# backplane.net
KiCad netlist of a schematic drawn in EAGLE
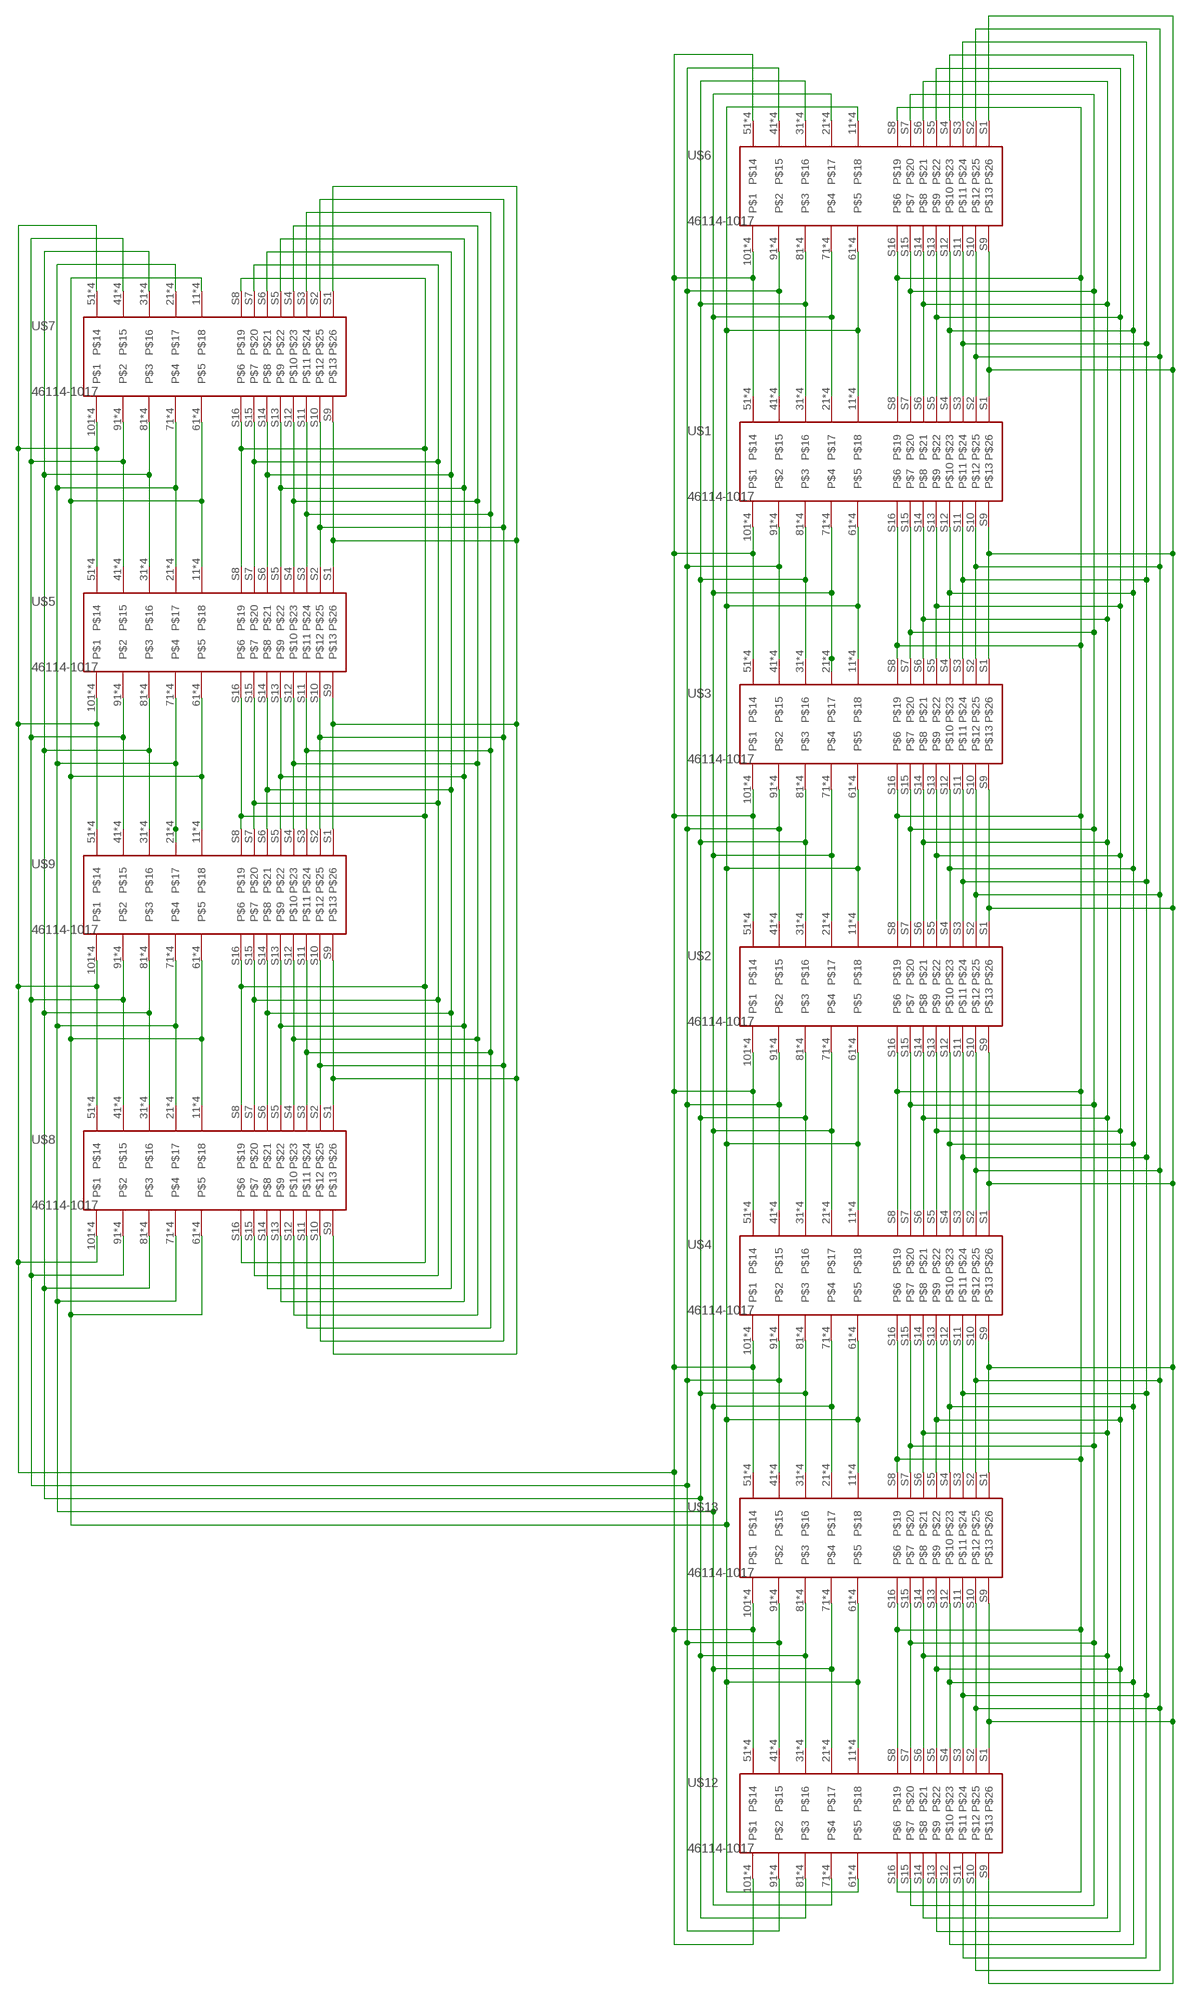
[diagram p0: schematic, sheet 1]

(export (version "E")
  (design (tool "Eeschema 10.0.6"))
  (components
    (comp (ref "U$1")
      (value "46114-1017")
      (footprint "eagle-import:46114-1017")
      (libsource (lib "eagle-import") (part "46114-1017"))
    )
    (comp (ref "U$2")
      (value "46114-1017")
      (footprint "eagle-import:46114-1017")
      (libsource (lib "eagle-import") (part "46114-1017"))
    )
    (comp (ref "U$3")
      (value "46114-1017")
      (footprint "eagle-import:46114-1017")
      (libsource (lib "eagle-import") (part "46114-1017"))
    )
    (comp (ref "U$4")
      (value "46114-1017")
      (footprint "eagle-import:46114-1017")
      (libsource (lib "eagle-import") (part "46114-1017"))
    )
    (comp (ref "U$5")
      (value "46114-1017")
      (footprint "eagle-import:46114-1017")
      (libsource (lib "eagle-import") (part "46114-1017"))
    )
    (comp (ref "U$6")
      (value "46114-1017")
      (footprint "eagle-import:46114-1017")
      (libsource (lib "eagle-import") (part "46114-1017"))
    )
    (comp (ref "U$7")
      (value "46114-1017")
      (footprint "eagle-import:46114-1017")
      (libsource (lib "eagle-import") (part "46114-1017"))
    )
    (comp (ref "U$8")
      (value "46114-1017")
      (footprint "eagle-import:46114-1017")
      (libsource (lib "eagle-import") (part "46114-1017"))
    )
    (comp (ref "U$9")
      (value "46114-1017")
      (footprint "eagle-import:46114-1017")
      (libsource (lib "eagle-import") (part "46114-1017"))
    )
    (comp (ref "U$12")
      (value "46114-1017")
      (footprint "eagle-import:46114-1017")
      (libsource (lib "eagle-import") (part "46114-1017"))
    )
    (comp (ref "U$13")
      (value "46114-1017")
      (footprint "eagle-import:46114-1017")
      (libsource (lib "eagle-import") (part "46114-1017"))
    )
  )
  (nets
    (net (code "1") (name "Net-(U$1-P$1-Pad101)") (class "Default")
      (node (ref "U$1") (pin "101") (pinfunction "P$1_101") (pintype "bidirectional"))
      (node (ref "U$1") (pin "102") (pinfunction "P$1_102") (pintype "bidirectional"))
      (node (ref "U$1") (pin "103") (pinfunction "P$1_103") (pintype "bidirectional"))
      (node (ref "U$1") (pin "104") (pinfunction "P$1_104") (pintype "bidirectional"))
      (node (ref "U$1") (pin "51") (pinfunction "P$14_51") (pintype "bidirectional"))
      (node (ref "U$1") (pin "52") (pinfunction "P$14_52") (pintype "bidirectional"))
      (node (ref "U$1") (pin "53") (pinfunction "P$14_53") (pintype "bidirectional"))
      (node (ref "U$1") (pin "54") (pinfunction "P$14_54") (pintype "bidirectional"))
      (node (ref "U$12") (pin "101") (pinfunction "P$1_101") (pintype "bidirectional"))
      (node (ref "U$12") (pin "102") (pinfunction "P$1_102") (pintype "bidirectional"))
      (node (ref "U$12") (pin "103") (pinfunction "P$1_103") (pintype "bidirectional"))
      (node (ref "U$12") (pin "104") (pinfunction "P$1_104") (pintype "bidirectional"))
      (node (ref "U$12") (pin "51") (pinfunction "P$14_51") (pintype "bidirectional"))
      (node (ref "U$12") (pin "52") (pinfunction "P$14_52") (pintype "bidirectional"))
      (node (ref "U$12") (pin "53") (pinfunction "P$14_53") (pintype "bidirectional"))
      (node (ref "U$12") (pin "54") (pinfunction "P$14_54") (pintype "bidirectional"))
      (node (ref "U$13") (pin "101") (pinfunction "P$1_101") (pintype "bidirectional"))
      (node (ref "U$13") (pin "102") (pinfunction "P$1_102") (pintype "bidirectional"))
      (node (ref "U$13") (pin "103") (pinfunction "P$1_103") (pintype "bidirectional"))
      (node (ref "U$13") (pin "104") (pinfunction "P$1_104") (pintype "bidirectional"))
      (node (ref "U$13") (pin "51") (pinfunction "P$14_51") (pintype "bidirectional"))
      (node (ref "U$13") (pin "52") (pinfunction "P$14_52") (pintype "bidirectional"))
      (node (ref "U$13") (pin "53") (pinfunction "P$14_53") (pintype "bidirectional"))
      (node (ref "U$13") (pin "54") (pinfunction "P$14_54") (pintype "bidirectional"))
      (node (ref "U$2") (pin "101") (pinfunction "P$1_101") (pintype "bidirectional"))
      (node (ref "U$2") (pin "102") (pinfunction "P$1_102") (pintype "bidirectional"))
      (node (ref "U$2") (pin "103") (pinfunction "P$1_103") (pintype "bidirectional"))
      (node (ref "U$2") (pin "104") (pinfunction "P$1_104") (pintype "bidirectional"))
      (node (ref "U$2") (pin "51") (pinfunction "P$14_51") (pintype "bidirectional"))
      (node (ref "U$2") (pin "52") (pinfunction "P$14_52") (pintype "bidirectional"))
      (node (ref "U$2") (pin "53") (pinfunction "P$14_53") (pintype "bidirectional"))
      (node (ref "U$2") (pin "54") (pinfunction "P$14_54") (pintype "bidirectional"))
      (node (ref "U$3") (pin "101") (pinfunction "P$1_101") (pintype "bidirectional"))
      (node (ref "U$3") (pin "102") (pinfunction "P$1_102") (pintype "bidirectional"))
      (node (ref "U$3") (pin "103") (pinfunction "P$1_103") (pintype "bidirectional"))
      (node (ref "U$3") (pin "104") (pinfunction "P$1_104") (pintype "bidirectional"))
      (node (ref "U$3") (pin "51") (pinfunction "P$14_51") (pintype "bidirectional"))
      (node (ref "U$3") (pin "52") (pinfunction "P$14_52") (pintype "bidirectional"))
      (node (ref "U$3") (pin "53") (pinfunction "P$14_53") (pintype "bidirectional"))
      (node (ref "U$3") (pin "54") (pinfunction "P$14_54") (pintype "bidirectional"))
      (node (ref "U$4") (pin "101") (pinfunction "P$1_101") (pintype "bidirectional"))
      (node (ref "U$4") (pin "102") (pinfunction "P$1_102") (pintype "bidirectional"))
      (node (ref "U$4") (pin "103") (pinfunction "P$1_103") (pintype "bidirectional"))
      (node (ref "U$4") (pin "104") (pinfunction "P$1_104") (pintype "bidirectional"))
      (node (ref "U$4") (pin "51") (pinfunction "P$14_51") (pintype "bidirectional"))
      (node (ref "U$4") (pin "52") (pinfunction "P$14_52") (pintype "bidirectional"))
      (node (ref "U$4") (pin "53") (pinfunction "P$14_53") (pintype "bidirectional"))
      (node (ref "U$4") (pin "54") (pinfunction "P$14_54") (pintype "bidirectional"))
      (node (ref "U$5") (pin "101") (pinfunction "P$1_101") (pintype "bidirectional"))
      (node (ref "U$5") (pin "102") (pinfunction "P$1_102") (pintype "bidirectional"))
      (node (ref "U$5") (pin "103") (pinfunction "P$1_103") (pintype "bidirectional"))
      (node (ref "U$5") (pin "104") (pinfunction "P$1_104") (pintype "bidirectional"))
      (node (ref "U$5") (pin "51") (pinfunction "P$14_51") (pintype "bidirectional"))
      (node (ref "U$5") (pin "52") (pinfunction "P$14_52") (pintype "bidirectional"))
      (node (ref "U$5") (pin "53") (pinfunction "P$14_53") (pintype "bidirectional"))
      (node (ref "U$5") (pin "54") (pinfunction "P$14_54") (pintype "bidirectional"))
      (node (ref "U$6") (pin "101") (pinfunction "P$1_101") (pintype "bidirectional"))
      (node (ref "U$6") (pin "102") (pinfunction "P$1_102") (pintype "bidirectional"))
      (node (ref "U$6") (pin "103") (pinfunction "P$1_103") (pintype "bidirectional"))
      (node (ref "U$6") (pin "104") (pinfunction "P$1_104") (pintype "bidirectional"))
      (node (ref "U$6") (pin "51") (pinfunction "P$14_51") (pintype "bidirectional"))
      (node (ref "U$6") (pin "52") (pinfunction "P$14_52") (pintype "bidirectional"))
      (node (ref "U$6") (pin "53") (pinfunction "P$14_53") (pintype "bidirectional"))
      (node (ref "U$6") (pin "54") (pinfunction "P$14_54") (pintype "bidirectional"))
      (node (ref "U$7") (pin "101") (pinfunction "P$1_101") (pintype "bidirectional"))
      (node (ref "U$7") (pin "102") (pinfunction "P$1_102") (pintype "bidirectional"))
      (node (ref "U$7") (pin "103") (pinfunction "P$1_103") (pintype "bidirectional"))
      (node (ref "U$7") (pin "104") (pinfunction "P$1_104") (pintype "bidirectional"))
      (node (ref "U$7") (pin "51") (pinfunction "P$14_51") (pintype "bidirectional"))
      (node (ref "U$7") (pin "52") (pinfunction "P$14_52") (pintype "bidirectional"))
      (node (ref "U$7") (pin "53") (pinfunction "P$14_53") (pintype "bidirectional"))
      (node (ref "U$7") (pin "54") (pinfunction "P$14_54") (pintype "bidirectional"))
      (node (ref "U$8") (pin "101") (pinfunction "P$1_101") (pintype "bidirectional"))
      (node (ref "U$8") (pin "102") (pinfunction "P$1_102") (pintype "bidirectional"))
      (node (ref "U$8") (pin "103") (pinfunction "P$1_103") (pintype "bidirectional"))
      (node (ref "U$8") (pin "104") (pinfunction "P$1_104") (pintype "bidirectional"))
      (node (ref "U$8") (pin "51") (pinfunction "P$14_51") (pintype "bidirectional"))
      (node (ref "U$8") (pin "52") (pinfunction "P$14_52") (pintype "bidirectional"))
      (node (ref "U$8") (pin "53") (pinfunction "P$14_53") (pintype "bidirectional"))
      (node (ref "U$8") (pin "54") (pinfunction "P$14_54") (pintype "bidirectional"))
      (node (ref "U$9") (pin "101") (pinfunction "P$1_101") (pintype "bidirectional"))
      (node (ref "U$9") (pin "102") (pinfunction "P$1_102") (pintype "bidirectional"))
      (node (ref "U$9") (pin "103") (pinfunction "P$1_103") (pintype "bidirectional"))
      (node (ref "U$9") (pin "104") (pinfunction "P$1_104") (pintype "bidirectional"))
      (node (ref "U$9") (pin "51") (pinfunction "P$14_51") (pintype "bidirectional"))
      (node (ref "U$9") (pin "52") (pinfunction "P$14_52") (pintype "bidirectional"))
      (node (ref "U$9") (pin "53") (pinfunction "P$14_53") (pintype "bidirectional"))
      (node (ref "U$9") (pin "54") (pinfunction "P$14_54") (pintype "bidirectional"))
    )
    (net (code "2") (name "Net-(U$1-P$10)") (class "Default")
      (node (ref "U$1") (pin "S12") (pinfunction "P$10_S12") (pintype "bidirectional"))
      (node (ref "U$1") (pin "S4") (pinfunction "P$23_S4") (pintype "bidirectional"))
      (node (ref "U$12") (pin "S12") (pinfunction "P$10_S12") (pintype "bidirectional"))
      (node (ref "U$12") (pin "S4") (pinfunction "P$23_S4") (pintype "bidirectional"))
      (node (ref "U$13") (pin "S12") (pinfunction "P$10_S12") (pintype "bidirectional"))
      (node (ref "U$13") (pin "S4") (pinfunction "P$23_S4") (pintype "bidirectional"))
      (node (ref "U$2") (pin "S12") (pinfunction "P$10_S12") (pintype "bidirectional"))
      (node (ref "U$2") (pin "S4") (pinfunction "P$23_S4") (pintype "bidirectional"))
      (node (ref "U$3") (pin "S12") (pinfunction "P$10_S12") (pintype "bidirectional"))
      (node (ref "U$3") (pin "S4") (pinfunction "P$23_S4") (pintype "bidirectional"))
      (node (ref "U$4") (pin "S12") (pinfunction "P$10_S12") (pintype "bidirectional"))
      (node (ref "U$4") (pin "S4") (pinfunction "P$23_S4") (pintype "bidirectional"))
      (node (ref "U$6") (pin "S12") (pinfunction "P$10_S12") (pintype "bidirectional"))
      (node (ref "U$6") (pin "S4") (pinfunction "P$23_S4") (pintype "bidirectional"))
    )
    (net (code "3") (name "Net-(U$1-P$11)") (class "Default")
      (node (ref "U$1") (pin "S11") (pinfunction "P$11_S11") (pintype "bidirectional"))
      (node (ref "U$1") (pin "S3") (pinfunction "P$24_S3") (pintype "bidirectional"))
      (node (ref "U$12") (pin "S11") (pinfunction "P$11_S11") (pintype "bidirectional"))
      (node (ref "U$12") (pin "S3") (pinfunction "P$24_S3") (pintype "bidirectional"))
      (node (ref "U$13") (pin "S11") (pinfunction "P$11_S11") (pintype "bidirectional"))
      (node (ref "U$13") (pin "S3") (pinfunction "P$24_S3") (pintype "bidirectional"))
      (node (ref "U$2") (pin "S11") (pinfunction "P$11_S11") (pintype "bidirectional"))
      (node (ref "U$2") (pin "S3") (pinfunction "P$24_S3") (pintype "bidirectional"))
      (node (ref "U$3") (pin "S11") (pinfunction "P$11_S11") (pintype "bidirectional"))
      (node (ref "U$3") (pin "S3") (pinfunction "P$24_S3") (pintype "bidirectional"))
      (node (ref "U$4") (pin "S11") (pinfunction "P$11_S11") (pintype "bidirectional"))
      (node (ref "U$4") (pin "S3") (pinfunction "P$24_S3") (pintype "bidirectional"))
      (node (ref "U$6") (pin "S11") (pinfunction "P$11_S11") (pintype "bidirectional"))
      (node (ref "U$6") (pin "S3") (pinfunction "P$24_S3") (pintype "bidirectional"))
    )
    (net (code "4") (name "Net-(U$1-P$12)") (class "Default")
      (node (ref "U$1") (pin "S10") (pinfunction "P$12_S10") (pintype "bidirectional"))
      (node (ref "U$1") (pin "S2") (pinfunction "P$25_S2") (pintype "bidirectional"))
      (node (ref "U$12") (pin "S10") (pinfunction "P$12_S10") (pintype "bidirectional"))
      (node (ref "U$12") (pin "S2") (pinfunction "P$25_S2") (pintype "bidirectional"))
      (node (ref "U$13") (pin "S10") (pinfunction "P$12_S10") (pintype "bidirectional"))
      (node (ref "U$13") (pin "S2") (pinfunction "P$25_S2") (pintype "bidirectional"))
      (node (ref "U$2") (pin "S10") (pinfunction "P$12_S10") (pintype "bidirectional"))
      (node (ref "U$2") (pin "S2") (pinfunction "P$25_S2") (pintype "bidirectional"))
      (node (ref "U$3") (pin "S10") (pinfunction "P$12_S10") (pintype "bidirectional"))
      (node (ref "U$3") (pin "S2") (pinfunction "P$25_S2") (pintype "bidirectional"))
      (node (ref "U$4") (pin "S10") (pinfunction "P$12_S10") (pintype "bidirectional"))
      (node (ref "U$4") (pin "S2") (pinfunction "P$25_S2") (pintype "bidirectional"))
      (node (ref "U$6") (pin "S10") (pinfunction "P$12_S10") (pintype "bidirectional"))
      (node (ref "U$6") (pin "S2") (pinfunction "P$25_S2") (pintype "bidirectional"))
    )
    (net (code "5") (name "Net-(U$1-P$13)") (class "Default")
      (node (ref "U$1") (pin "S1") (pinfunction "P$26_S1") (pintype "bidirectional"))
      (node (ref "U$1") (pin "S9") (pinfunction "P$13_S9") (pintype "bidirectional"))
      (node (ref "U$12") (pin "S1") (pinfunction "P$26_S1") (pintype "bidirectional"))
      (node (ref "U$12") (pin "S9") (pinfunction "P$13_S9") (pintype "bidirectional"))
      (node (ref "U$13") (pin "S1") (pinfunction "P$26_S1") (pintype "bidirectional"))
      (node (ref "U$13") (pin "S9") (pinfunction "P$13_S9") (pintype "bidirectional"))
      (node (ref "U$2") (pin "S1") (pinfunction "P$26_S1") (pintype "bidirectional"))
      (node (ref "U$2") (pin "S9") (pinfunction "P$13_S9") (pintype "bidirectional"))
      (node (ref "U$3") (pin "S1") (pinfunction "P$26_S1") (pintype "bidirectional"))
      (node (ref "U$3") (pin "S9") (pinfunction "P$13_S9") (pintype "bidirectional"))
      (node (ref "U$4") (pin "S1") (pinfunction "P$26_S1") (pintype "bidirectional"))
      (node (ref "U$4") (pin "S9") (pinfunction "P$13_S9") (pintype "bidirectional"))
      (node (ref "U$6") (pin "S1") (pinfunction "P$26_S1") (pintype "bidirectional"))
      (node (ref "U$6") (pin "S9") (pinfunction "P$13_S9") (pintype "bidirectional"))
    )
    (net (code "6") (name "Net-(U$1-P$15-Pad41)") (class "Default")
      (node (ref "U$1") (pin "41") (pinfunction "P$15_41") (pintype "bidirectional"))
      (node (ref "U$1") (pin "42") (pinfunction "P$15_42") (pintype "bidirectional"))
      (node (ref "U$1") (pin "43") (pinfunction "P$15_43") (pintype "bidirectional"))
      (node (ref "U$1") (pin "44") (pinfunction "P$15_44") (pintype "bidirectional"))
      (node (ref "U$1") (pin "91") (pinfunction "P$2_91") (pintype "bidirectional"))
      (node (ref "U$1") (pin "92") (pinfunction "P$2_92") (pintype "bidirectional"))
      (node (ref "U$1") (pin "93") (pinfunction "P$2_93") (pintype "bidirectional"))
      (node (ref "U$1") (pin "94") (pinfunction "P$2_94") (pintype "bidirectional"))
      (node (ref "U$12") (pin "41") (pinfunction "P$15_41") (pintype "bidirectional"))
      (node (ref "U$12") (pin "42") (pinfunction "P$15_42") (pintype "bidirectional"))
      (node (ref "U$12") (pin "43") (pinfunction "P$15_43") (pintype "bidirectional"))
      (node (ref "U$12") (pin "44") (pinfunction "P$15_44") (pintype "bidirectional"))
      (node (ref "U$12") (pin "91") (pinfunction "P$2_91") (pintype "bidirectional"))
      (node (ref "U$12") (pin "92") (pinfunction "P$2_92") (pintype "bidirectional"))
      (node (ref "U$12") (pin "93") (pinfunction "P$2_93") (pintype "bidirectional"))
      (node (ref "U$12") (pin "94") (pinfunction "P$2_94") (pintype "bidirectional"))
      (node (ref "U$13") (pin "41") (pinfunction "P$15_41") (pintype "bidirectional"))
      (node (ref "U$13") (pin "42") (pinfunction "P$15_42") (pintype "bidirectional"))
      (node (ref "U$13") (pin "43") (pinfunction "P$15_43") (pintype "bidirectional"))
      (node (ref "U$13") (pin "44") (pinfunction "P$15_44") (pintype "bidirectional"))
      (node (ref "U$13") (pin "91") (pinfunction "P$2_91") (pintype "bidirectional"))
      (node (ref "U$13") (pin "92") (pinfunction "P$2_92") (pintype "bidirectional"))
      (node (ref "U$13") (pin "93") (pinfunction "P$2_93") (pintype "bidirectional"))
      (node (ref "U$13") (pin "94") (pinfunction "P$2_94") (pintype "bidirectional"))
      (node (ref "U$2") (pin "41") (pinfunction "P$15_41") (pintype "bidirectional"))
      (node (ref "U$2") (pin "42") (pinfunction "P$15_42") (pintype "bidirectional"))
      (node (ref "U$2") (pin "43") (pinfunction "P$15_43") (pintype "bidirectional"))
      (node (ref "U$2") (pin "44") (pinfunction "P$15_44") (pintype "bidirectional"))
      (node (ref "U$2") (pin "91") (pinfunction "P$2_91") (pintype "bidirectional"))
      (node (ref "U$2") (pin "92") (pinfunction "P$2_92") (pintype "bidirectional"))
      (node (ref "U$2") (pin "93") (pinfunction "P$2_93") (pintype "bidirectional"))
      (node (ref "U$2") (pin "94") (pinfunction "P$2_94") (pintype "bidirectional"))
      (node (ref "U$3") (pin "41") (pinfunction "P$15_41") (pintype "bidirectional"))
      (node (ref "U$3") (pin "42") (pinfunction "P$15_42") (pintype "bidirectional"))
      (node (ref "U$3") (pin "43") (pinfunction "P$15_43") (pintype "bidirectional"))
      (node (ref "U$3") (pin "44") (pinfunction "P$15_44") (pintype "bidirectional"))
      (node (ref "U$3") (pin "91") (pinfunction "P$2_91") (pintype "bidirectional"))
      (node (ref "U$3") (pin "92") (pinfunction "P$2_92") (pintype "bidirectional"))
      (node (ref "U$3") (pin "93") (pinfunction "P$2_93") (pintype "bidirectional"))
      (node (ref "U$3") (pin "94") (pinfunction "P$2_94") (pintype "bidirectional"))
      (node (ref "U$4") (pin "41") (pinfunction "P$15_41") (pintype "bidirectional"))
      (node (ref "U$4") (pin "42") (pinfunction "P$15_42") (pintype "bidirectional"))
      (node (ref "U$4") (pin "43") (pinfunction "P$15_43") (pintype "bidirectional"))
      (node (ref "U$4") (pin "44") (pinfunction "P$15_44") (pintype "bidirectional"))
      (node (ref "U$4") (pin "91") (pinfunction "P$2_91") (pintype "bidirectional"))
      (node (ref "U$4") (pin "92") (pinfunction "P$2_92") (pintype "bidirectional"))
      (node (ref "U$4") (pin "93") (pinfunction "P$2_93") (pintype "bidirectional"))
      (node (ref "U$4") (pin "94") (pinfunction "P$2_94") (pintype "bidirectional"))
      (node (ref "U$5") (pin "41") (pinfunction "P$15_41") (pintype "bidirectional"))
      (node (ref "U$5") (pin "42") (pinfunction "P$15_42") (pintype "bidirectional"))
      (node (ref "U$5") (pin "43") (pinfunction "P$15_43") (pintype "bidirectional"))
      (node (ref "U$5") (pin "44") (pinfunction "P$15_44") (pintype "bidirectional"))
      (node (ref "U$5") (pin "91") (pinfunction "P$2_91") (pintype "bidirectional"))
      (node (ref "U$5") (pin "92") (pinfunction "P$2_92") (pintype "bidirectional"))
      (node (ref "U$5") (pin "93") (pinfunction "P$2_93") (pintype "bidirectional"))
      (node (ref "U$5") (pin "94") (pinfunction "P$2_94") (pintype "bidirectional"))
      (node (ref "U$6") (pin "41") (pinfunction "P$15_41") (pintype "bidirectional"))
      (node (ref "U$6") (pin "42") (pinfunction "P$15_42") (pintype "bidirectional"))
      (node (ref "U$6") (pin "43") (pinfunction "P$15_43") (pintype "bidirectional"))
      (node (ref "U$6") (pin "44") (pinfunction "P$15_44") (pintype "bidirectional"))
      (node (ref "U$6") (pin "91") (pinfunction "P$2_91") (pintype "bidirectional"))
      (node (ref "U$6") (pin "92") (pinfunction "P$2_92") (pintype "bidirectional"))
      (node (ref "U$6") (pin "93") (pinfunction "P$2_93") (pintype "bidirectional"))
      (node (ref "U$6") (pin "94") (pinfunction "P$2_94") (pintype "bidirectional"))
      (node (ref "U$7") (pin "41") (pinfunction "P$15_41") (pintype "bidirectional"))
      (node (ref "U$7") (pin "42") (pinfunction "P$15_42") (pintype "bidirectional"))
      (node (ref "U$7") (pin "43") (pinfunction "P$15_43") (pintype "bidirectional"))
      (node (ref "U$7") (pin "44") (pinfunction "P$15_44") (pintype "bidirectional"))
      (node (ref "U$7") (pin "91") (pinfunction "P$2_91") (pintype "bidirectional"))
      (node (ref "U$7") (pin "92") (pinfunction "P$2_92") (pintype "bidirectional"))
      (node (ref "U$7") (pin "93") (pinfunction "P$2_93") (pintype "bidirectional"))
      (node (ref "U$7") (pin "94") (pinfunction "P$2_94") (pintype "bidirectional"))
      (node (ref "U$8") (pin "41") (pinfunction "P$15_41") (pintype "bidirectional"))
      (node (ref "U$8") (pin "42") (pinfunction "P$15_42") (pintype "bidirectional"))
      (node (ref "U$8") (pin "43") (pinfunction "P$15_43") (pintype "bidirectional"))
      (node (ref "U$8") (pin "44") (pinfunction "P$15_44") (pintype "bidirectional"))
      (node (ref "U$8") (pin "91") (pinfunction "P$2_91") (pintype "bidirectional"))
      (node (ref "U$8") (pin "92") (pinfunction "P$2_92") (pintype "bidirectional"))
      (node (ref "U$8") (pin "93") (pinfunction "P$2_93") (pintype "bidirectional"))
      (node (ref "U$8") (pin "94") (pinfunction "P$2_94") (pintype "bidirectional"))
      (node (ref "U$9") (pin "41") (pinfunction "P$15_41") (pintype "bidirectional"))
      (node (ref "U$9") (pin "42") (pinfunction "P$15_42") (pintype "bidirectional"))
      (node (ref "U$9") (pin "43") (pinfunction "P$15_43") (pintype "bidirectional"))
      (node (ref "U$9") (pin "44") (pinfunction "P$15_44") (pintype "bidirectional"))
      (node (ref "U$9") (pin "91") (pinfunction "P$2_91") (pintype "bidirectional"))
      (node (ref "U$9") (pin "92") (pinfunction "P$2_92") (pintype "bidirectional"))
      (node (ref "U$9") (pin "93") (pinfunction "P$2_93") (pintype "bidirectional"))
      (node (ref "U$9") (pin "94") (pinfunction "P$2_94") (pintype "bidirectional"))
    )
    (net (code "7") (name "Net-(U$1-P$16-Pad31)") (class "Default")
      (node (ref "U$1") (pin "31") (pinfunction "P$16_31") (pintype "bidirectional"))
      (node (ref "U$1") (pin "32") (pinfunction "P$16_32") (pintype "bidirectional"))
      (node (ref "U$1") (pin "33") (pinfunction "P$16_33") (pintype "bidirectional"))
      (node (ref "U$1") (pin "34") (pinfunction "P$16_34") (pintype "bidirectional"))
      (node (ref "U$1") (pin "81") (pinfunction "P$3_81") (pintype "bidirectional"))
      (node (ref "U$1") (pin "82") (pinfunction "P$3_82") (pintype "bidirectional"))
      (node (ref "U$1") (pin "83") (pinfunction "P$3_83") (pintype "bidirectional"))
      (node (ref "U$1") (pin "84") (pinfunction "P$3_84") (pintype "bidirectional"))
      (node (ref "U$12") (pin "31") (pinfunction "P$16_31") (pintype "bidirectional"))
      (node (ref "U$12") (pin "32") (pinfunction "P$16_32") (pintype "bidirectional"))
      (node (ref "U$12") (pin "33") (pinfunction "P$16_33") (pintype "bidirectional"))
      (node (ref "U$12") (pin "34") (pinfunction "P$16_34") (pintype "bidirectional"))
      (node (ref "U$12") (pin "81") (pinfunction "P$3_81") (pintype "bidirectional"))
      (node (ref "U$12") (pin "82") (pinfunction "P$3_82") (pintype "bidirectional"))
      (node (ref "U$12") (pin "83") (pinfunction "P$3_83") (pintype "bidirectional"))
      (node (ref "U$12") (pin "84") (pinfunction "P$3_84") (pintype "bidirectional"))
      (node (ref "U$13") (pin "31") (pinfunction "P$16_31") (pintype "bidirectional"))
      (node (ref "U$13") (pin "32") (pinfunction "P$16_32") (pintype "bidirectional"))
      (node (ref "U$13") (pin "33") (pinfunction "P$16_33") (pintype "bidirectional"))
      (node (ref "U$13") (pin "34") (pinfunction "P$16_34") (pintype "bidirectional"))
      (node (ref "U$13") (pin "81") (pinfunction "P$3_81") (pintype "bidirectional"))
      (node (ref "U$13") (pin "82") (pinfunction "P$3_82") (pintype "bidirectional"))
      (node (ref "U$13") (pin "83") (pinfunction "P$3_83") (pintype "bidirectional"))
      (node (ref "U$13") (pin "84") (pinfunction "P$3_84") (pintype "bidirectional"))
      (node (ref "U$2") (pin "31") (pinfunction "P$16_31") (pintype "bidirectional"))
      (node (ref "U$2") (pin "32") (pinfunction "P$16_32") (pintype "bidirectional"))
      (node (ref "U$2") (pin "33") (pinfunction "P$16_33") (pintype "bidirectional"))
      (node (ref "U$2") (pin "34") (pinfunction "P$16_34") (pintype "bidirectional"))
      (node (ref "U$2") (pin "81") (pinfunction "P$3_81") (pintype "bidirectional"))
      (node (ref "U$2") (pin "82") (pinfunction "P$3_82") (pintype "bidirectional"))
      (node (ref "U$2") (pin "83") (pinfunction "P$3_83") (pintype "bidirectional"))
      (node (ref "U$2") (pin "84") (pinfunction "P$3_84") (pintype "bidirectional"))
      (node (ref "U$3") (pin "31") (pinfunction "P$16_31") (pintype "bidirectional"))
      (node (ref "U$3") (pin "32") (pinfunction "P$16_32") (pintype "bidirectional"))
      (node (ref "U$3") (pin "33") (pinfunction "P$16_33") (pintype "bidirectional"))
      (node (ref "U$3") (pin "34") (pinfunction "P$16_34") (pintype "bidirectional"))
      (node (ref "U$3") (pin "81") (pinfunction "P$3_81") (pintype "bidirectional"))
      (node (ref "U$3") (pin "82") (pinfunction "P$3_82") (pintype "bidirectional"))
      (node (ref "U$3") (pin "83") (pinfunction "P$3_83") (pintype "bidirectional"))
      (node (ref "U$3") (pin "84") (pinfunction "P$3_84") (pintype "bidirectional"))
      (node (ref "U$4") (pin "31") (pinfunction "P$16_31") (pintype "bidirectional"))
      (node (ref "U$4") (pin "32") (pinfunction "P$16_32") (pintype "bidirectional"))
      (node (ref "U$4") (pin "33") (pinfunction "P$16_33") (pintype "bidirectional"))
      (node (ref "U$4") (pin "34") (pinfunction "P$16_34") (pintype "bidirectional"))
      (node (ref "U$4") (pin "81") (pinfunction "P$3_81") (pintype "bidirectional"))
      (node (ref "U$4") (pin "82") (pinfunction "P$3_82") (pintype "bidirectional"))
      (node (ref "U$4") (pin "83") (pinfunction "P$3_83") (pintype "bidirectional"))
      (node (ref "U$4") (pin "84") (pinfunction "P$3_84") (pintype "bidirectional"))
      (node (ref "U$5") (pin "31") (pinfunction "P$16_31") (pintype "bidirectional"))
      (node (ref "U$5") (pin "32") (pinfunction "P$16_32") (pintype "bidirectional"))
      (node (ref "U$5") (pin "33") (pinfunction "P$16_33") (pintype "bidirectional"))
      (node (ref "U$5") (pin "34") (pinfunction "P$16_34") (pintype "bidirectional"))
      (node (ref "U$5") (pin "81") (pinfunction "P$3_81") (pintype "bidirectional"))
      (node (ref "U$5") (pin "82") (pinfunction "P$3_82") (pintype "bidirectional"))
      (node (ref "U$5") (pin "83") (pinfunction "P$3_83") (pintype "bidirectional"))
      (node (ref "U$5") (pin "84") (pinfunction "P$3_84") (pintype "bidirectional"))
      (node (ref "U$6") (pin "31") (pinfunction "P$16_31") (pintype "bidirectional"))
      (node (ref "U$6") (pin "32") (pinfunction "P$16_32") (pintype "bidirectional"))
      (node (ref "U$6") (pin "33") (pinfunction "P$16_33") (pintype "bidirectional"))
      (node (ref "U$6") (pin "34") (pinfunction "P$16_34") (pintype "bidirectional"))
      (node (ref "U$6") (pin "81") (pinfunction "P$3_81") (pintype "bidirectional"))
      (node (ref "U$6") (pin "82") (pinfunction "P$3_82") (pintype "bidirectional"))
      (node (ref "U$6") (pin "83") (pinfunction "P$3_83") (pintype "bidirectional"))
      (node (ref "U$6") (pin "84") (pinfunction "P$3_84") (pintype "bidirectional"))
      (node (ref "U$7") (pin "31") (pinfunction "P$16_31") (pintype "bidirectional"))
      (node (ref "U$7") (pin "32") (pinfunction "P$16_32") (pintype "bidirectional"))
      (node (ref "U$7") (pin "33") (pinfunction "P$16_33") (pintype "bidirectional"))
      (node (ref "U$7") (pin "34") (pinfunction "P$16_34") (pintype "bidirectional"))
      (node (ref "U$7") (pin "81") (pinfunction "P$3_81") (pintype "bidirectional"))
      (node (ref "U$7") (pin "82") (pinfunction "P$3_82") (pintype "bidirectional"))
      (node (ref "U$7") (pin "83") (pinfunction "P$3_83") (pintype "bidirectional"))
      (node (ref "U$7") (pin "84") (pinfunction "P$3_84") (pintype "bidirectional"))
      (node (ref "U$8") (pin "31") (pinfunction "P$16_31") (pintype "bidirectional"))
      (node (ref "U$8") (pin "32") (pinfunction "P$16_32") (pintype "bidirectional"))
      (node (ref "U$8") (pin "33") (pinfunction "P$16_33") (pintype "bidirectional"))
      (node (ref "U$8") (pin "34") (pinfunction "P$16_34") (pintype "bidirectional"))
      (node (ref "U$8") (pin "81") (pinfunction "P$3_81") (pintype "bidirectional"))
      (node (ref "U$8") (pin "82") (pinfunction "P$3_82") (pintype "bidirectional"))
      (node (ref "U$8") (pin "83") (pinfunction "P$3_83") (pintype "bidirectional"))
      (node (ref "U$8") (pin "84") (pinfunction "P$3_84") (pintype "bidirectional"))
      (node (ref "U$9") (pin "31") (pinfunction "P$16_31") (pintype "bidirectional"))
      (node (ref "U$9") (pin "32") (pinfunction "P$16_32") (pintype "bidirectional"))
      (node (ref "U$9") (pin "33") (pinfunction "P$16_33") (pintype "bidirectional"))
      (node (ref "U$9") (pin "34") (pinfunction "P$16_34") (pintype "bidirectional"))
      (node (ref "U$9") (pin "81") (pinfunction "P$3_81") (pintype "bidirectional"))
      (node (ref "U$9") (pin "82") (pinfunction "P$3_82") (pintype "bidirectional"))
      (node (ref "U$9") (pin "83") (pinfunction "P$3_83") (pintype "bidirectional"))
      (node (ref "U$9") (pin "84") (pinfunction "P$3_84") (pintype "bidirectional"))
    )
    (net (code "8") (name "Net-(U$1-P$17-Pad21)") (class "Default")
      (node (ref "U$1") (pin "21") (pinfunction "P$17_21") (pintype "bidirectional"))
      (node (ref "U$1") (pin "22") (pinfunction "P$17_22") (pintype "bidirectional"))
      (node (ref "U$1") (pin "23") (pinfunction "P$17_23") (pintype "bidirectional"))
      (node (ref "U$1") (pin "24") (pinfunction "P$17_24") (pintype "bidirectional"))
      (node (ref "U$1") (pin "71") (pinfunction "P$4_71") (pintype "bidirectional"))
      (node (ref "U$1") (pin "72") (pinfunction "P$4_72") (pintype "bidirectional"))
      (node (ref "U$1") (pin "73") (pinfunction "P$4_73") (pintype "bidirectional"))
      (node (ref "U$1") (pin "74") (pinfunction "P$4_74") (pintype "bidirectional"))
      (node (ref "U$12") (pin "21") (pinfunction "P$17_21") (pintype "bidirectional"))
      (node (ref "U$12") (pin "22") (pinfunction "P$17_22") (pintype "bidirectional"))
      (node (ref "U$12") (pin "23") (pinfunction "P$17_23") (pintype "bidirectional"))
      (node (ref "U$12") (pin "24") (pinfunction "P$17_24") (pintype "bidirectional"))
      (node (ref "U$12") (pin "71") (pinfunction "P$4_71") (pintype "bidirectional"))
      (node (ref "U$12") (pin "72") (pinfunction "P$4_72") (pintype "bidirectional"))
      (node (ref "U$12") (pin "73") (pinfunction "P$4_73") (pintype "bidirectional"))
      (node (ref "U$12") (pin "74") (pinfunction "P$4_74") (pintype "bidirectional"))
      (node (ref "U$13") (pin "21") (pinfunction "P$17_21") (pintype "bidirectional"))
      (node (ref "U$13") (pin "22") (pinfunction "P$17_22") (pintype "bidirectional"))
      (node (ref "U$13") (pin "23") (pinfunction "P$17_23") (pintype "bidirectional"))
      (node (ref "U$13") (pin "24") (pinfunction "P$17_24") (pintype "bidirectional"))
      (node (ref "U$13") (pin "71") (pinfunction "P$4_71") (pintype "bidirectional"))
      (node (ref "U$13") (pin "72") (pinfunction "P$4_72") (pintype "bidirectional"))
      (node (ref "U$13") (pin "73") (pinfunction "P$4_73") (pintype "bidirectional"))
      (node (ref "U$13") (pin "74") (pinfunction "P$4_74") (pintype "bidirectional"))
      (node (ref "U$2") (pin "21") (pinfunction "P$17_21") (pintype "bidirectional"))
      (node (ref "U$2") (pin "22") (pinfunction "P$17_22") (pintype "bidirectional"))
      (node (ref "U$2") (pin "23") (pinfunction "P$17_23") (pintype "bidirectional"))
      (node (ref "U$2") (pin "24") (pinfunction "P$17_24") (pintype "bidirectional"))
      (node (ref "U$2") (pin "71") (pinfunction "P$4_71") (pintype "bidirectional"))
      (node (ref "U$2") (pin "72") (pinfunction "P$4_72") (pintype "bidirectional"))
      (node (ref "U$2") (pin "73") (pinfunction "P$4_73") (pintype "bidirectional"))
      (node (ref "U$2") (pin "74") (pinfunction "P$4_74") (pintype "bidirectional"))
      (node (ref "U$3") (pin "21") (pinfunction "P$17_21") (pintype "bidirectional"))
      (node (ref "U$3") (pin "22") (pinfunction "P$17_22") (pintype "bidirectional"))
      (node (ref "U$3") (pin "23") (pinfunction "P$17_23") (pintype "bidirectional"))
      (node (ref "U$3") (pin "24") (pinfunction "P$17_24") (pintype "bidirectional"))
      (node (ref "U$3") (pin "71") (pinfunction "P$4_71") (pintype "bidirectional"))
      (node (ref "U$3") (pin "72") (pinfunction "P$4_72") (pintype "bidirectional"))
      (node (ref "U$3") (pin "73") (pinfunction "P$4_73") (pintype "bidirectional"))
      (node (ref "U$3") (pin "74") (pinfunction "P$4_74") (pintype "bidirectional"))
      (node (ref "U$4") (pin "21") (pinfunction "P$17_21") (pintype "bidirectional"))
      (node (ref "U$4") (pin "22") (pinfunction "P$17_22") (pintype "bidirectional"))
      (node (ref "U$4") (pin "23") (pinfunction "P$17_23") (pintype "bidirectional"))
      (node (ref "U$4") (pin "24") (pinfunction "P$17_24") (pintype "bidirectional"))
      (node (ref "U$4") (pin "71") (pinfunction "P$4_71") (pintype "bidirectional"))
      (node (ref "U$4") (pin "72") (pinfunction "P$4_72") (pintype "bidirectional"))
      (node (ref "U$4") (pin "73") (pinfunction "P$4_73") (pintype "bidirectional"))
      (node (ref "U$4") (pin "74") (pinfunction "P$4_74") (pintype "bidirectional"))
      (node (ref "U$5") (pin "21") (pinfunction "P$17_21") (pintype "bidirectional"))
      (node (ref "U$5") (pin "22") (pinfunction "P$17_22") (pintype "bidirectional"))
      (node (ref "U$5") (pin "23") (pinfunction "P$17_23") (pintype "bidirectional"))
      (node (ref "U$5") (pin "24") (pinfunction "P$17_24") (pintype "bidirectional"))
      (node (ref "U$5") (pin "71") (pinfunction "P$4_71") (pintype "bidirectional"))
      (node (ref "U$5") (pin "72") (pinfunction "P$4_72") (pintype "bidirectional"))
      (node (ref "U$5") (pin "73") (pinfunction "P$4_73") (pintype "bidirectional"))
      (node (ref "U$5") (pin "74") (pinfunction "P$4_74") (pintype "bidirectional"))
      (node (ref "U$6") (pin "21") (pinfunction "P$17_21") (pintype "bidirectional"))
      (node (ref "U$6") (pin "22") (pinfunction "P$17_22") (pintype "bidirectional"))
      (node (ref "U$6") (pin "23") (pinfunction "P$17_23") (pintype "bidirectional"))
      (node (ref "U$6") (pin "24") (pinfunction "P$17_24") (pintype "bidirectional"))
      (node (ref "U$6") (pin "71") (pinfunction "P$4_71") (pintype "bidirectional"))
      (node (ref "U$6") (pin "72") (pinfunction "P$4_72") (pintype "bidirectional"))
      (node (ref "U$6") (pin "73") (pinfunction "P$4_73") (pintype "bidirectional"))
      (node (ref "U$6") (pin "74") (pinfunction "P$4_74") (pintype "bidirectional"))
      (node (ref "U$7") (pin "21") (pinfunction "P$17_21") (pintype "bidirectional"))
      (node (ref "U$7") (pin "22") (pinfunction "P$17_22") (pintype "bidirectional"))
      (node (ref "U$7") (pin "23") (pinfunction "P$17_23") (pintype "bidirectional"))
      (node (ref "U$7") (pin "24") (pinfunction "P$17_24") (pintype "bidirectional"))
      (node (ref "U$7") (pin "71") (pinfunction "P$4_71") (pintype "bidirectional"))
      (node (ref "U$7") (pin "72") (pinfunction "P$4_72") (pintype "bidirectional"))
      (node (ref "U$7") (pin "73") (pinfunction "P$4_73") (pintype "bidirectional"))
      (node (ref "U$7") (pin "74") (pinfunction "P$4_74") (pintype "bidirectional"))
      (node (ref "U$8") (pin "21") (pinfunction "P$17_21") (pintype "bidirectional"))
      (node (ref "U$8") (pin "22") (pinfunction "P$17_22") (pintype "bidirectional"))
      (node (ref "U$8") (pin "23") (pinfunction "P$17_23") (pintype "bidirectional"))
      (node (ref "U$8") (pin "24") (pinfunction "P$17_24") (pintype "bidirectional"))
      (node (ref "U$8") (pin "71") (pinfunction "P$4_71") (pintype "bidirectional"))
      (node (ref "U$8") (pin "72") (pinfunction "P$4_72") (pintype "bidirectional"))
      (node (ref "U$8") (pin "73") (pinfunction "P$4_73") (pintype "bidirectional"))
      (node (ref "U$8") (pin "74") (pinfunction "P$4_74") (pintype "bidirectional"))
      (node (ref "U$9") (pin "21") (pinfunction "P$17_21") (pintype "bidirectional"))
      (node (ref "U$9") (pin "22") (pinfunction "P$17_22") (pintype "bidirectional"))
      (node (ref "U$9") (pin "23") (pinfunction "P$17_23") (pintype "bidirectional"))
      (node (ref "U$9") (pin "24") (pinfunction "P$17_24") (pintype "bidirectional"))
      (node (ref "U$9") (pin "71") (pinfunction "P$4_71") (pintype "bidirectional"))
      (node (ref "U$9") (pin "72") (pinfunction "P$4_72") (pintype "bidirectional"))
      (node (ref "U$9") (pin "73") (pinfunction "P$4_73") (pintype "bidirectional"))
      (node (ref "U$9") (pin "74") (pinfunction "P$4_74") (pintype "bidirectional"))
    )
    (net (code "9") (name "Net-(U$1-P$18-Pad11)") (class "Default")
      (node (ref "U$1") (pin "11") (pinfunction "P$18_11") (pintype "bidirectional"))
      (node (ref "U$1") (pin "12") (pinfunction "P$18_12") (pintype "bidirectional"))
      (node (ref "U$1") (pin "13") (pinfunction "P$18_13") (pintype "bidirectional"))
      (node (ref "U$1") (pin "14") (pinfunction "P$18_14") (pintype "bidirectional"))
      (node (ref "U$1") (pin "61") (pinfunction "P$5_61") (pintype "bidirectional"))
      (node (ref "U$1") (pin "62") (pinfunction "P$5_62") (pintype "bidirectional"))
      (node (ref "U$1") (pin "63") (pinfunction "P$5_63") (pintype "bidirectional"))
      (node (ref "U$1") (pin "64") (pinfunction "P$5_64") (pintype "bidirectional"))
      (node (ref "U$12") (pin "11") (pinfunction "P$18_11") (pintype "bidirectional"))
      (node (ref "U$12") (pin "12") (pinfunction "P$18_12") (pintype "bidirectional"))
      (node (ref "U$12") (pin "13") (pinfunction "P$18_13") (pintype "bidirectional"))
      (node (ref "U$12") (pin "14") (pinfunction "P$18_14") (pintype "bidirectional"))
      (node (ref "U$12") (pin "61") (pinfunction "P$5_61") (pintype "bidirectional"))
      (node (ref "U$12") (pin "62") (pinfunction "P$5_62") (pintype "bidirectional"))
      (node (ref "U$12") (pin "63") (pinfunction "P$5_63") (pintype "bidirectional"))
      (node (ref "U$12") (pin "64") (pinfunction "P$5_64") (pintype "bidirectional"))
      (node (ref "U$13") (pin "11") (pinfunction "P$18_11") (pintype "bidirectional"))
      (node (ref "U$13") (pin "12") (pinfunction "P$18_12") (pintype "bidirectional"))
      (node (ref "U$13") (pin "13") (pinfunction "P$18_13") (pintype "bidirectional"))
      (node (ref "U$13") (pin "14") (pinfunction "P$18_14") (pintype "bidirectional"))
      (node (ref "U$13") (pin "61") (pinfunction "P$5_61") (pintype "bidirectional"))
      (node (ref "U$13") (pin "62") (pinfunction "P$5_62") (pintype "bidirectional"))
      (node (ref "U$13") (pin "63") (pinfunction "P$5_63") (pintype "bidirectional"))
      (node (ref "U$13") (pin "64") (pinfunction "P$5_64") (pintype "bidirectional"))
      (node (ref "U$2") (pin "11") (pinfunction "P$18_11") (pintype "bidirectional"))
      (node (ref "U$2") (pin "12") (pinfunction "P$18_12") (pintype "bidirectional"))
      (node (ref "U$2") (pin "13") (pinfunction "P$18_13") (pintype "bidirectional"))
      (node (ref "U$2") (pin "14") (pinfunction "P$18_14") (pintype "bidirectional"))
      (node (ref "U$2") (pin "61") (pinfunction "P$5_61") (pintype "bidirectional"))
      (node (ref "U$2") (pin "62") (pinfunction "P$5_62") (pintype "bidirectional"))
      (node (ref "U$2") (pin "63") (pinfunction "P$5_63") (pintype "bidirectional"))
      (node (ref "U$2") (pin "64") (pinfunction "P$5_64") (pintype "bidirectional"))
      (node (ref "U$3") (pin "11") (pinfunction "P$18_11") (pintype "bidirectional"))
      (node (ref "U$3") (pin "12") (pinfunction "P$18_12") (pintype "bidirectional"))
      (node (ref "U$3") (pin "13") (pinfunction "P$18_13") (pintype "bidirectional"))
      (node (ref "U$3") (pin "14") (pinfunction "P$18_14") (pintype "bidirectional"))
      (node (ref "U$3") (pin "61") (pinfunction "P$5_61") (pintype "bidirectional"))
      (node (ref "U$3") (pin "62") (pinfunction "P$5_62") (pintype "bidirectional"))
      (node (ref "U$3") (pin "63") (pinfunction "P$5_63") (pintype "bidirectional"))
      (node (ref "U$3") (pin "64") (pinfunction "P$5_64") (pintype "bidirectional"))
      (node (ref "U$4") (pin "11") (pinfunction "P$18_11") (pintype "bidirectional"))
      (node (ref "U$4") (pin "12") (pinfunction "P$18_12") (pintype "bidirectional"))
      (node (ref "U$4") (pin "13") (pinfunction "P$18_13") (pintype "bidirectional"))
      (node (ref "U$4") (pin "14") (pinfunction "P$18_14") (pintype "bidirectional"))
      (node (ref "U$4") (pin "61") (pinfunction "P$5_61") (pintype "bidirectional"))
      (node (ref "U$4") (pin "62") (pinfunction "P$5_62") (pintype "bidirectional"))
      (node (ref "U$4") (pin "63") (pinfunction "P$5_63") (pintype "bidirectional"))
      (node (ref "U$4") (pin "64") (pinfunction "P$5_64") (pintype "bidirectional"))
      (node (ref "U$5") (pin "11") (pinfunction "P$18_11") (pintype "bidirectional"))
      (node (ref "U$5") (pin "12") (pinfunction "P$18_12") (pintype "bidirectional"))
      (node (ref "U$5") (pin "13") (pinfunction "P$18_13") (pintype "bidirectional"))
      (node (ref "U$5") (pin "14") (pinfunction "P$18_14") (pintype "bidirectional"))
      (node (ref "U$5") (pin "61") (pinfunction "P$5_61") (pintype "bidirectional"))
      (node (ref "U$5") (pin "62") (pinfunction "P$5_62") (pintype "bidirectional"))
      (node (ref "U$5") (pin "63") (pinfunction "P$5_63") (pintype "bidirectional"))
      (node (ref "U$5") (pin "64") (pinfunction "P$5_64") (pintype "bidirectional"))
      (node (ref "U$6") (pin "11") (pinfunction "P$18_11") (pintype "bidirectional"))
      (node (ref "U$6") (pin "12") (pinfunction "P$18_12") (pintype "bidirectional"))
      (node (ref "U$6") (pin "13") (pinfunction "P$18_13") (pintype "bidirectional"))
      (node (ref "U$6") (pin "14") (pinfunction "P$18_14") (pintype "bidirectional"))
      (node (ref "U$6") (pin "61") (pinfunction "P$5_61") (pintype "bidirectional"))
      (node (ref "U$6") (pin "62") (pinfunction "P$5_62") (pintype "bidirectional"))
      (node (ref "U$6") (pin "63") (pinfunction "P$5_63") (pintype "bidirectional"))
      (node (ref "U$6") (pin "64") (pinfunction "P$5_64") (pintype "bidirectional"))
      (node (ref "U$7") (pin "11") (pinfunction "P$18_11") (pintype "bidirectional"))
      (node (ref "U$7") (pin "12") (pinfunction "P$18_12") (pintype "bidirectional"))
      (node (ref "U$7") (pin "13") (pinfunction "P$18_13") (pintype "bidirectional"))
      (node (ref "U$7") (pin "14") (pinfunction "P$18_14") (pintype "bidirectional"))
      (node (ref "U$7") (pin "61") (pinfunction "P$5_61") (pintype "bidirectional"))
      (node (ref "U$7") (pin "62") (pinfunction "P$5_62") (pintype "bidirectional"))
      (node (ref "U$7") (pin "63") (pinfunction "P$5_63") (pintype "bidirectional"))
      (node (ref "U$7") (pin "64") (pinfunction "P$5_64") (pintype "bidirectional"))
      (node (ref "U$8") (pin "11") (pinfunction "P$18_11") (pintype "bidirectional"))
      (node (ref "U$8") (pin "12") (pinfunction "P$18_12") (pintype "bidirectional"))
      (node (ref "U$8") (pin "13") (pinfunction "P$18_13") (pintype "bidirectional"))
      (node (ref "U$8") (pin "14") (pinfunction "P$18_14") (pintype "bidirectional"))
      (node (ref "U$8") (pin "61") (pinfunction "P$5_61") (pintype "bidirectional"))
      (node (ref "U$8") (pin "62") (pinfunction "P$5_62") (pintype "bidirectional"))
      (node (ref "U$8") (pin "63") (pinfunction "P$5_63") (pintype "bidirectional"))
      (node (ref "U$8") (pin "64") (pinfunction "P$5_64") (pintype "bidirectional"))
      (node (ref "U$9") (pin "11") (pinfunction "P$18_11") (pintype "bidirectional"))
      (node (ref "U$9") (pin "12") (pinfunction "P$18_12") (pintype "bidirectional"))
      (node (ref "U$9") (pin "13") (pinfunction "P$18_13") (pintype "bidirectional"))
      (node (ref "U$9") (pin "14") (pinfunction "P$18_14") (pintype "bidirectional"))
      (node (ref "U$9") (pin "61") (pinfunction "P$5_61") (pintype "bidirectional"))
      (node (ref "U$9") (pin "62") (pinfunction "P$5_62") (pintype "bidirectional"))
      (node (ref "U$9") (pin "63") (pinfunction "P$5_63") (pintype "bidirectional"))
      (node (ref "U$9") (pin "64") (pinfunction "P$5_64") (pintype "bidirectional"))
    )
    (net (code "10") (name "Net-(U$1-P$19)") (class "Default")
      (node (ref "U$1") (pin "S16") (pinfunction "P$6_S16") (pintype "bidirectional"))
      (node (ref "U$1") (pin "S8") (pinfunction "P$19_S8") (pintype "bidirectional"))
      (node (ref "U$12") (pin "S16") (pinfunction "P$6_S16") (pintype "bidirectional"))
      (node (ref "U$12") (pin "S8") (pinfunction "P$19_S8") (pintype "bidirectional"))
      (node (ref "U$13") (pin "S16") (pinfunction "P$6_S16") (pintype "bidirectional"))
      (node (ref "U$13") (pin "S8") (pinfunction "P$19_S8") (pintype "bidirectional"))
      (node (ref "U$2") (pin "S16") (pinfunction "P$6_S16") (pintype "bidirectional"))
      (node (ref "U$2") (pin "S8") (pinfunction "P$19_S8") (pintype "bidirectional"))
      (node (ref "U$3") (pin "S16") (pinfunction "P$6_S16") (pintype "bidirectional"))
      (node (ref "U$3") (pin "S8") (pinfunction "P$19_S8") (pintype "bidirectional"))
      (node (ref "U$4") (pin "S16") (pinfunction "P$6_S16") (pintype "bidirectional"))
      (node (ref "U$4") (pin "S8") (pinfunction "P$19_S8") (pintype "bidirectional"))
      (node (ref "U$6") (pin "S16") (pinfunction "P$6_S16") (pintype "bidirectional"))
      (node (ref "U$6") (pin "S8") (pinfunction "P$19_S8") (pintype "bidirectional"))
    )
    (net (code "11") (name "Net-(U$1-P$20)") (class "Default")
      (node (ref "U$1") (pin "S15") (pinfunction "P$7_S15") (pintype "bidirectional"))
      (node (ref "U$1") (pin "S7") (pinfunction "P$20_S7") (pintype "bidirectional"))
      (node (ref "U$12") (pin "S15") (pinfunction "P$7_S15") (pintype "bidirectional"))
      (node (ref "U$12") (pin "S7") (pinfunction "P$20_S7") (pintype "bidirectional"))
      (node (ref "U$13") (pin "S15") (pinfunction "P$7_S15") (pintype "bidirectional"))
      (node (ref "U$13") (pin "S7") (pinfunction "P$20_S7") (pintype "bidirectional"))
      (node (ref "U$2") (pin "S15") (pinfunction "P$7_S15") (pintype "bidirectional"))
      (node (ref "U$2") (pin "S7") (pinfunction "P$20_S7") (pintype "bidirectional"))
      (node (ref "U$3") (pin "S15") (pinfunction "P$7_S15") (pintype "bidirectional"))
      (node (ref "U$3") (pin "S7") (pinfunction "P$20_S7") (pintype "bidirectional"))
      (node (ref "U$4") (pin "S15") (pinfunction "P$7_S15") (pintype "bidirectional"))
      (node (ref "U$4") (pin "S7") (pinfunction "P$20_S7") (pintype "bidirectional"))
      (node (ref "U$6") (pin "S15") (pinfunction "P$7_S15") (pintype "bidirectional"))
      (node (ref "U$6") (pin "S7") (pinfunction "P$20_S7") (pintype "bidirectional"))
    )
    (net (code "12") (name "Net-(U$1-P$21)") (class "Default")
      (node (ref "U$1") (pin "S14") (pinfunction "P$8_S14") (pintype "bidirectional"))
      (node (ref "U$1") (pin "S6") (pinfunction "P$21_S6") (pintype "bidirectional"))
      (node (ref "U$12") (pin "S14") (pinfunction "P$8_S14") (pintype "bidirectional"))
      (node (ref "U$12") (pin "S6") (pinfunction "P$21_S6") (pintype "bidirectional"))
      (node (ref "U$13") (pin "S14") (pinfunction "P$8_S14") (pintype "bidirectional"))
      (node (ref "U$13") (pin "S6") (pinfunction "P$21_S6") (pintype "bidirectional"))
      (node (ref "U$2") (pin "S14") (pinfunction "P$8_S14") (pintype "bidirectional"))
      (node (ref "U$2") (pin "S6") (pinfunction "P$21_S6") (pintype "bidirectional"))
      (node (ref "U$3") (pin "S14") (pinfunction "P$8_S14") (pintype "bidirectional"))
      (node (ref "U$3") (pin "S6") (pinfunction "P$21_S6") (pintype "bidirectional"))
      (node (ref "U$4") (pin "S14") (pinfunction "P$8_S14") (pintype "bidirectional"))
      (node (ref "U$4") (pin "S6") (pinfunction "P$21_S6") (pintype "bidirectional"))
      (node (ref "U$6") (pin "S14") (pinfunction "P$8_S14") (pintype "bidirectional"))
      (node (ref "U$6") (pin "S6") (pinfunction "P$21_S6") (pintype "bidirectional"))
    )
    (net (code "13") (name "Net-(U$1-P$22)") (class "Default")
      (node (ref "U$1") (pin "S13") (pinfunction "P$9_S13") (pintype "bidirectional"))
      (node (ref "U$1") (pin "S5") (pinfunction "P$22_S5") (pintype "bidirectional"))
      (node (ref "U$12") (pin "S13") (pinfunction "P$9_S13") (pintype "bidirectional"))
      (node (ref "U$12") (pin "S5") (pinfunction "P$22_S5") (pintype "bidirectional"))
      (node (ref "U$13") (pin "S13") (pinfunction "P$9_S13") (pintype "bidirectional"))
      (node (ref "U$13") (pin "S5") (pinfunction "P$22_S5") (pintype "bidirectional"))
      (node (ref "U$2") (pin "S13") (pinfunction "P$9_S13") (pintype "bidirectional"))
      (node (ref "U$2") (pin "S5") (pinfunction "P$22_S5") (pintype "bidirectional"))
      (node (ref "U$3") (pin "S13") (pinfunction "P$9_S13") (pintype "bidirectional"))
      (node (ref "U$3") (pin "S5") (pinfunction "P$22_S5") (pintype "bidirectional"))
      (node (ref "U$4") (pin "S13") (pinfunction "P$9_S13") (pintype "bidirectional"))
      (node (ref "U$4") (pin "S5") (pinfunction "P$22_S5") (pintype "bidirectional"))
      (node (ref "U$6") (pin "S13") (pinfunction "P$9_S13") (pintype "bidirectional"))
      (node (ref "U$6") (pin "S5") (pinfunction "P$22_S5") (pintype "bidirectional"))
    )
    (net (code "14") (name "Net-(U$5-P$10)") (class "Default")
      (node (ref "U$5") (pin "S12") (pinfunction "P$10_S12") (pintype "bidirectional"))
      (node (ref "U$5") (pin "S4") (pinfunction "P$23_S4") (pintype "bidirectional"))
      (node (ref "U$7") (pin "S12") (pinfunction "P$10_S12") (pintype "bidirectional"))
      (node (ref "U$7") (pin "S4") (pinfunction "P$23_S4") (pintype "bidirectional"))
      (node (ref "U$8") (pin "S12") (pinfunction "P$10_S12") (pintype "bidirectional"))
      (node (ref "U$8") (pin "S4") (pinfunction "P$23_S4") (pintype "bidirectional"))
      (node (ref "U$9") (pin "S12") (pinfunction "P$10_S12") (pintype "bidirectional"))
      (node (ref "U$9") (pin "S4") (pinfunction "P$23_S4") (pintype "bidirectional"))
    )
    (net (code "15") (name "Net-(U$5-P$11)") (class "Default")
      (node (ref "U$5") (pin "S11") (pinfunction "P$11_S11") (pintype "bidirectional"))
      (node (ref "U$5") (pin "S3") (pinfunction "P$24_S3") (pintype "bidirectional"))
      (node (ref "U$7") (pin "S11") (pinfunction "P$11_S11") (pintype "bidirectional"))
      (node (ref "U$7") (pin "S3") (pinfunction "P$24_S3") (pintype "bidirectional"))
      (node (ref "U$8") (pin "S11") (pinfunction "P$11_S11") (pintype "bidirectional"))
      (node (ref "U$8") (pin "S3") (pinfunction "P$24_S3") (pintype "bidirectional"))
      (node (ref "U$9") (pin "S11") (pinfunction "P$11_S11") (pintype "bidirectional"))
      (node (ref "U$9") (pin "S3") (pinfunction "P$24_S3") (pintype "bidirectional"))
    )
    (net (code "16") (name "Net-(U$5-P$12)") (class "Default")
      (node (ref "U$5") (pin "S10") (pinfunction "P$12_S10") (pintype "bidirectional"))
      (node (ref "U$5") (pin "S2") (pinfunction "P$25_S2") (pintype "bidirectional"))
      (node (ref "U$7") (pin "S10") (pinfunction "P$12_S10") (pintype "bidirectional"))
      (node (ref "U$7") (pin "S2") (pinfunction "P$25_S2") (pintype "bidirectional"))
      (node (ref "U$8") (pin "S10") (pinfunction "P$12_S10") (pintype "bidirectional"))
      (node (ref "U$8") (pin "S2") (pinfunction "P$25_S2") (pintype "bidirectional"))
      (node (ref "U$9") (pin "S10") (pinfunction "P$12_S10") (pintype "bidirectional"))
      (node (ref "U$9") (pin "S2") (pinfunction "P$25_S2") (pintype "bidirectional"))
    )
    (net (code "17") (name "Net-(U$5-P$13)") (class "Default")
      (node (ref "U$5") (pin "S1") (pinfunction "P$26_S1") (pintype "bidirectional"))
      (node (ref "U$5") (pin "S9") (pinfunction "P$13_S9") (pintype "bidirectional"))
      (node (ref "U$7") (pin "S1") (pinfunction "P$26_S1") (pintype "bidirectional"))
      (node (ref "U$7") (pin "S9") (pinfunction "P$13_S9") (pintype "bidirectional"))
      (node (ref "U$8") (pin "S1") (pinfunction "P$26_S1") (pintype "bidirectional"))
      (node (ref "U$8") (pin "S9") (pinfunction "P$13_S9") (pintype "bidirectional"))
      (node (ref "U$9") (pin "S1") (pinfunction "P$26_S1") (pintype "bidirectional"))
      (node (ref "U$9") (pin "S9") (pinfunction "P$13_S9") (pintype "bidirectional"))
    )
    (net (code "18") (name "Net-(U$5-P$19)") (class "Default")
      (node (ref "U$5") (pin "S16") (pinfunction "P$6_S16") (pintype "bidirectional"))
      (node (ref "U$5") (pin "S8") (pinfunction "P$19_S8") (pintype "bidirectional"))
      (node (ref "U$7") (pin "S16") (pinfunction "P$6_S16") (pintype "bidirectional"))
      (node (ref "U$7") (pin "S8") (pinfunction "P$19_S8") (pintype "bidirectional"))
      (node (ref "U$8") (pin "S16") (pinfunction "P$6_S16") (pintype "bidirectional"))
      (node (ref "U$8") (pin "S8") (pinfunction "P$19_S8") (pintype "bidirectional"))
      (node (ref "U$9") (pin "S16") (pinfunction "P$6_S16") (pintype "bidirectional"))
      (node (ref "U$9") (pin "S8") (pinfunction "P$19_S8") (pintype "bidirectional"))
    )
    (net (code "19") (name "Net-(U$5-P$20)") (class "Default")
      (node (ref "U$5") (pin "S15") (pinfunction "P$7_S15") (pintype "bidirectional"))
      (node (ref "U$5") (pin "S7") (pinfunction "P$20_S7") (pintype "bidirectional"))
      (node (ref "U$7") (pin "S15") (pinfunction "P$7_S15") (pintype "bidirectional"))
      (node (ref "U$7") (pin "S7") (pinfunction "P$20_S7") (pintype "bidirectional"))
      (node (ref "U$8") (pin "S15") (pinfunction "P$7_S15") (pintype "bidirectional"))
      (node (ref "U$8") (pin "S7") (pinfunction "P$20_S7") (pintype "bidirectional"))
      (node (ref "U$9") (pin "S15") (pinfunction "P$7_S15") (pintype "bidirectional"))
      (node (ref "U$9") (pin "S7") (pinfunction "P$20_S7") (pintype "bidirectional"))
    )
    (net (code "20") (name "Net-(U$5-P$21)") (class "Default")
      (node (ref "U$5") (pin "S14") (pinfunction "P$8_S14") (pintype "bidirectional"))
      (node (ref "U$5") (pin "S6") (pinfunction "P$21_S6") (pintype "bidirectional"))
      (node (ref "U$7") (pin "S14") (pinfunction "P$8_S14") (pintype "bidirectional"))
      (node (ref "U$7") (pin "S6") (pinfunction "P$21_S6") (pintype "bidirectional"))
      (node (ref "U$8") (pin "S14") (pinfunction "P$8_S14") (pintype "bidirectional"))
      (node (ref "U$8") (pin "S6") (pinfunction "P$21_S6") (pintype "bidirectional"))
      (node (ref "U$9") (pin "S14") (pinfunction "P$8_S14") (pintype "bidirectional"))
      (node (ref "U$9") (pin "S6") (pinfunction "P$21_S6") (pintype "bidirectional"))
    )
    (net (code "21") (name "Net-(U$5-P$22)") (class "Default")
      (node (ref "U$5") (pin "S13") (pinfunction "P$9_S13") (pintype "bidirectional"))
      (node (ref "U$5") (pin "S5") (pinfunction "P$22_S5") (pintype "bidirectional"))
      (node (ref "U$7") (pin "S13") (pinfunction "P$9_S13") (pintype "bidirectional"))
      (node (ref "U$7") (pin "S5") (pinfunction "P$22_S5") (pintype "bidirectional"))
      (node (ref "U$8") (pin "S13") (pinfunction "P$9_S13") (pintype "bidirectional"))
      (node (ref "U$8") (pin "S5") (pinfunction "P$22_S5") (pintype "bidirectional"))
      (node (ref "U$9") (pin "S13") (pinfunction "P$9_S13") (pintype "bidirectional"))
      (node (ref "U$9") (pin "S5") (pinfunction "P$22_S5") (pintype "bidirectional"))
    )
  )
)
